# Ctrl.net
KiCad netlist of a schematic drawn in Altium Designer
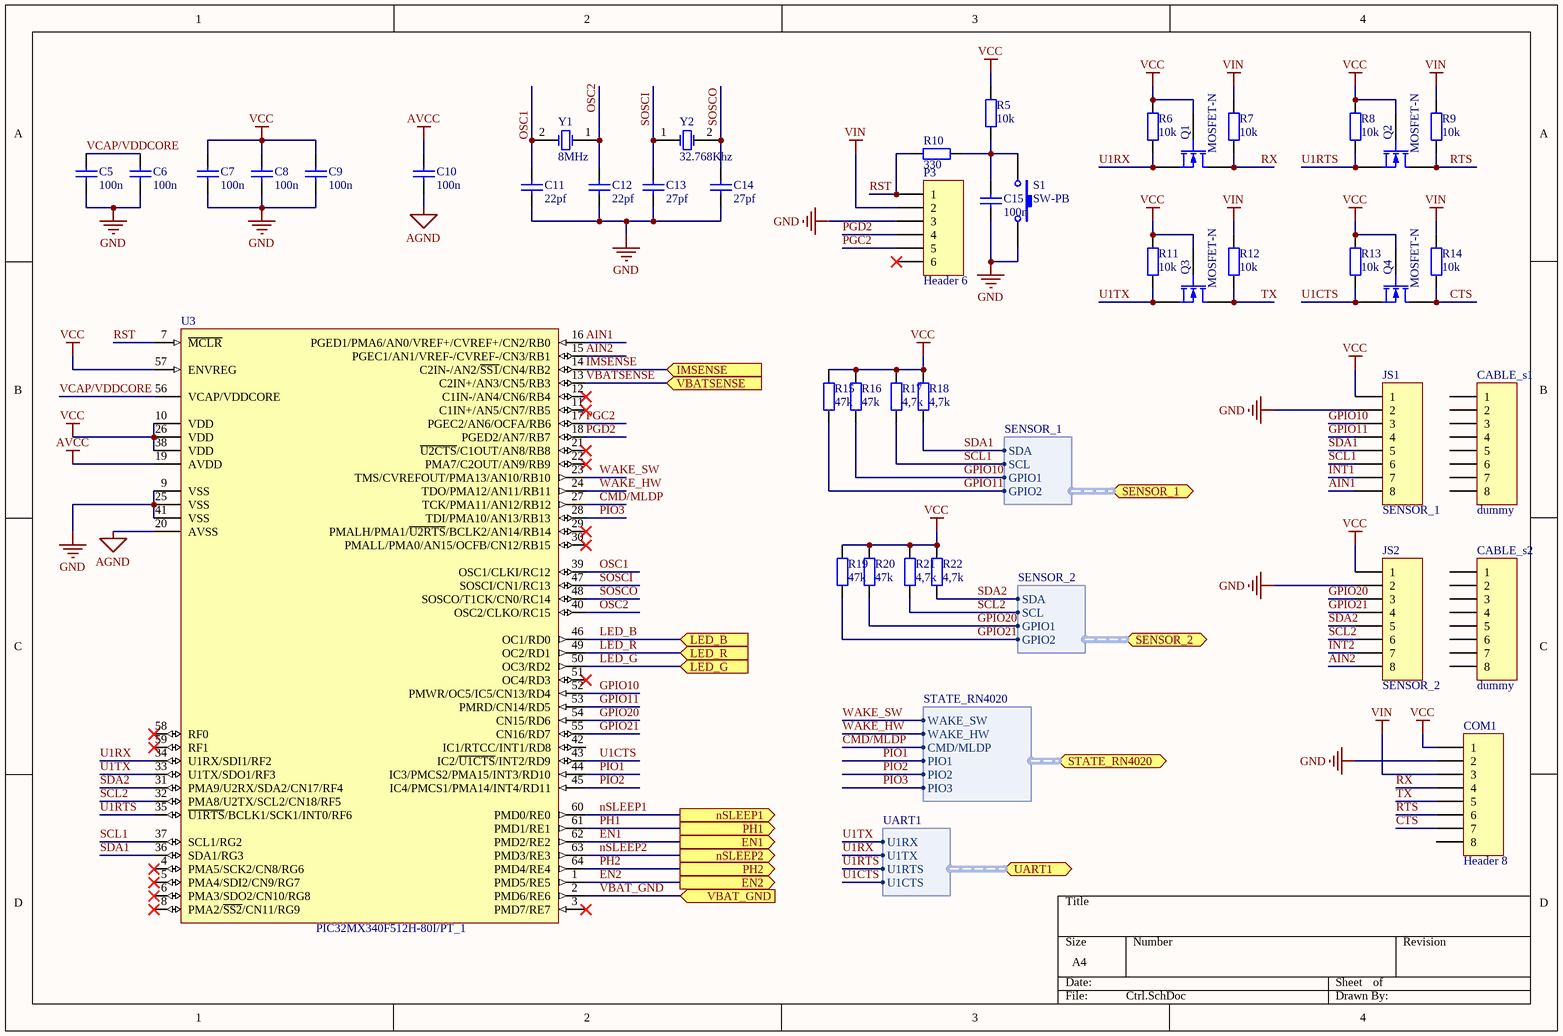
[diagram p0: Ctrl.SchDoc]

(export (version "E")
  (design (tool "Eeschema 10.0.6"))
  (components
    (comp (ref "C5")
      (value "100n")
      (footprint "RES 0603/1608")
      (libsource (lib "Miscellaneous Devices") (part "Cap"))
    )
    (comp (ref "C6")
      (value "100n")
      (footprint "RES 0603/1608")
      (libsource (lib "Miscellaneous Devices") (part "Cap"))
    )
    (comp (ref "C7")
      (value "100n")
      (footprint "RES 0603/1608")
      (libsource (lib "Miscellaneous Devices") (part "Cap"))
    )
    (comp (ref "C8")
      (value "100n")
      (footprint "RES 0603/1608")
      (libsource (lib "Miscellaneous Devices") (part "Cap"))
    )
    (comp (ref "C9")
      (value "100n")
      (footprint "RES 0603/1608")
      (libsource (lib "Miscellaneous Devices") (part "Cap"))
    )
    (comp (ref "C10")
      (value "100n")
      (footprint "RES 0603/1608")
      (libsource (lib "Miscellaneous Devices") (part "Cap"))
    )
    (comp (ref "C11")
      (value "22pf")
      (footprint "RES 0603/1608")
      (description "Condensateur céramique multicouche CMS, 0805 [2012 Metric], 22 pF, 50 V, ± 5%, C0G / NP0")
      (libsource (lib "Miscellaneous Devices") (part "Cap"))
    )
    (comp (ref "C12")
      (value "22pf")
      (footprint "RES 0603/1608")
      (description "Condensateur céramique multicouche CMS, 0805 [2012 Metric], 22 pF, 50 V, ± 5%, C0G / NP0")
      (libsource (lib "Miscellaneous Devices") (part "Cap"))
    )
    (comp (ref "C13")
      (value "27pf")
      (footprint "RES 0603/1608")
      (description "Condensateur céramique multicouche CMS, 0805 [2012 Metric], 27 pF, 50 V, ± 5%, C0G / NP0")
      (libsource (lib "Miscellaneous Devices") (part "Cap"))
    )
    (comp (ref "C14")
      (value "27pf")
      (footprint "RES 0603/1608")
      (description "Condensateur céramique multicouche CMS, 0805 [2012 Metric], 27 pF, 50 V, ± 5%, C0G / NP0")
      (libsource (lib "Miscellaneous Devices") (part "Cap"))
    )
    (comp (ref "C15")
      (value "100n")
      (footprint "RES 0603/1608")
      (libsource (lib "Miscellaneous Devices") (part "Cap"))
    )
    (comp (ref "CABLE_s1") (value "dummy") (libsource (lib "Miscellaneous Connectors") (part "Header 8")))
    (comp (ref "CABLE_s2") (value "dummy") (libsource (lib "Miscellaneous Connectors") (part "Header 8")))
    (comp (ref "COM1")
      (value "Header 8")
      (footprint "7-215460-8")
      (libsource (lib "Miscellaneous Connectors") (part "Header 8"))
    )
    (comp (ref "JS1")
      (value "SENSOR_1")
      (footprint "7-215460-8")
      (libsource (lib "Miscellaneous Connectors") (part "Header 8"))
    )
    (comp (ref "JS2")
      (value "SENSOR_2")
      (footprint "7-215460-8")
      (libsource (lib "Miscellaneous Connectors") (part "Header 8"))
    )
    (comp (ref "P3")
      (value "Header 6")
      (footprint "HDR1X6")
      (description "Header, 6-Pin")
      (libsource (lib "Miscellaneous Connectors") (part "Header 6"))
    )
    (comp (ref "Q1")
      (value "MOSFET-N")
      (footprint "SOT-23")
      (description "Transistor MOSFET, Canal N, 200 mA, 60 V, 2.7 ohm, 10 V, 1.2 V")
      (libsource (lib "Miscellaneous Devices") (part "MOSFET-N"))
    )
    (comp (ref "Q2")
      (value "MOSFET-N")
      (footprint "SOT-23")
      (description "Transistor MOSFET, Canal N, 200 mA, 60 V, 2.7 ohm, 10 V, 1.2 V")
      (libsource (lib "Miscellaneous Devices") (part "MOSFET-N"))
    )
    (comp (ref "Q3")
      (value "MOSFET-N")
      (footprint "SOT-23")
      (description "Transistor MOSFET, Canal N, 200 mA, 60 V, 2.7 ohm, 10 V, 1.2 V")
      (libsource (lib "Miscellaneous Devices") (part "MOSFET-N"))
    )
    (comp (ref "Q4")
      (value "MOSFET-N")
      (footprint "SOT-23")
      (description "Transistor MOSFET, Canal N, 200 mA, 60 V, 2.7 ohm, 10 V, 1.2 V")
      (libsource (lib "Miscellaneous Devices") (part "MOSFET-N"))
    )
    (comp (ref "R5")
      (value "10k")
      (footprint "RES 0603/1608")
      (description "Résistance à puce CMS, Couche épaisse, 10 kohm, 150 V, 0805")
      (libsource (lib "Miscellaneous Devices") (part "Res2"))
    )
    (comp (ref "R6")
      (value "10k")
      (footprint "RES 0603/1608")
      (description "Résistance à puce CMS, Couche épaisse, 10 kohm, 150 V, 0805")
      (libsource (lib "Miscellaneous Devices") (part "Res2"))
    )
    (comp (ref "R7")
      (value "10k")
      (footprint "RES 0603/1608")
      (description "Résistance à puce CMS, Couche épaisse, 10 kohm, 150 V, 0805")
      (libsource (lib "Miscellaneous Devices") (part "Res2"))
    )
    (comp (ref "R8")
      (value "10k")
      (footprint "RES 0603/1608")
      (description "Résistance à puce CMS, Couche épaisse, 10 kohm, 150 V, 0805")
      (libsource (lib "Miscellaneous Devices") (part "Res2"))
    )
    (comp (ref "R9")
      (value "10k")
      (footprint "RES 0603/1608")
      (description "Résistance à puce CMS, Couche épaisse, 10 kohm, 150 V, 0805")
      (libsource (lib "Miscellaneous Devices") (part "Res2"))
    )
    (comp (ref "R10") (value "330") (footprint "RES 0603/1608") (libsource (lib "") (part "Res2_1")))
    (comp (ref "R11")
      (value "10k")
      (footprint "RES 0603/1608")
      (description "Résistance à puce CMS, Couche épaisse, 10 kohm, 150 V, 0805")
      (libsource (lib "Miscellaneous Devices") (part "Res2"))
    )
    (comp (ref "R12")
      (value "10k")
      (footprint "RES 0603/1608")
      (description "Résistance à puce CMS, Couche épaisse, 10 kohm, 150 V, 0805")
      (libsource (lib "Miscellaneous Devices") (part "Res2"))
    )
    (comp (ref "R13")
      (value "10k")
      (footprint "RES 0603/1608")
      (description "Résistance à puce CMS, Couche épaisse, 10 kohm, 150 V, 0805")
      (libsource (lib "Miscellaneous Devices") (part "Res2"))
    )
    (comp (ref "R14")
      (value "10k")
      (footprint "RES 0603/1608")
      (description "Résistance à puce CMS, Couche épaisse, 10 kohm, 150 V, 0805")
      (libsource (lib "Miscellaneous Devices") (part "Res2"))
    )
    (comp (ref "R15")
      (value "47k")
      (footprint "RES 0603/1608")
      (description "Résistance à puce CMS, Couche épaisse, 47 kohm, 150 V, 0805 [2012 Metric], 125 mW, ± 1%, Série RC")
      (libsource (lib "Miscellaneous Devices") (part "Res2"))
    )
    (comp (ref "R16")
      (value "47k")
      (footprint "RES 0603/1608")
      (description "Résistance à puce CMS, Couche épaisse, 47 kohm, 150 V, 0805 [2012 Metric], 125 mW, ± 1%, Série RC")
      (libsource (lib "Miscellaneous Devices") (part "Res2"))
    )
    (comp (ref "R17")
      (value "4,7k")
      (footprint "RES 0603/1608")
      (description "Résistance à puce CMS, Couche épaisse, 4.7 kohm, 150 V, 0805 [2012 Metric], 125 mW, ± 5%, Série RC")
      (libsource (lib "Miscellaneous Devices") (part "Res2"))
    )
    (comp (ref "R18")
      (value "4,7k")
      (footprint "RES 0603/1608")
      (description "Résistance à puce CMS, Couche épaisse, 4.7 kohm, 150 V, 0805 [2012 Metric], 125 mW, ± 5%, Série RC")
      (libsource (lib "Miscellaneous Devices") (part "Res2"))
    )
    (comp (ref "R19")
      (value "47k")
      (footprint "RES 0603/1608")
      (description "Résistance à puce CMS, Couche épaisse, 47 kohm, 150 V, 0805 [2012 Metric], 125 mW, ± 1%, Série RC")
      (libsource (lib "Miscellaneous Devices") (part "Res2"))
    )
    (comp (ref "R20")
      (value "47k")
      (footprint "RES 0603/1608")
      (description "Résistance à puce CMS, Couche épaisse, 47 kohm, 150 V, 0805 [2012 Metric], 125 mW, ± 1%, Série RC")
      (libsource (lib "Miscellaneous Devices") (part "Res2"))
    )
    (comp (ref "R21")
      (value "4,7k")
      (footprint "RES 0603/1608")
      (description "Résistance à puce CMS, Couche épaisse, 4.7 kohm, 150 V, 0805 [2012 Metric], 125 mW, ± 5%, Série RC")
      (libsource (lib "Miscellaneous Devices") (part "Res2"))
    )
    (comp (ref "R22")
      (value "4,7k")
      (footprint "RES 0603/1608")
      (description "Résistance à puce CMS, Couche épaisse, 4.7 kohm, 150 V, 0805 [2012 Metric], 125 mW, ± 5%, Série RC")
      (libsource (lib "Miscellaneous Devices") (part "Res2"))
    )
    (comp (ref "S1")
      (value "SW-PB")
      (footprint "Button")
      (description "Commutateur tactile, Non lumineux, 12 V, 50 mA, 100 gf, CMS, Série DTSZML-6")
      (libsource (lib "Miscellaneous Devices") (part "SW-PB"))
    )
    (comp (ref "U3")
      (value "PIC32MX340F512H-80I/PT_1")
      (footprint "TSQFP50P1200X1200X120-64N")
      (description "High Performance 80 MHz MIPS-Based 32-Bit Flash Microcontroller, 512KB Program Memory, 64-pin TQFP")
      (libsource (lib "ComponentLib") (part "PIC32MX340F512H-80I/PT_1"))
    )
    (comp (ref "Y1")
      (value "8MHz")
      (footprint "XTAL_HC-49/SM")
      (libsource (lib "Miscellaneous Devices") (part "XTAL"))
    )
    (comp (ref "Y2")
      (value "32.768Khz")
      (footprint "XTAL_AB26T")
      (libsource (lib "Miscellaneous Devices") (part "XTAL"))
    )
  )
  (nets
    (net (code "5") (name "/AIN1") (class "Default")
      (node (ref "JS1") (pin "8") (pinfunction "8_8") (pintype "passive"))
      (node (ref "U3") (pin "16") (pinfunction "PGED1/PMA6/AN0/VREF+/CVREF+/CN2/RB0_16") (pintype "input"))
    )
    (net (code "6") (name "/AIN2") (class "Default")
      (node (ref "JS2") (pin "8") (pinfunction "8_8") (pintype "passive"))
      (node (ref "U3") (pin "15") (pinfunction "PGEC1/AN1/VREF-/CVREF-/CN3/RB1_15") (pintype "bidirectional"))
    )
    (net (code "7") (name "/CMD{slash}MLDP") (class "Default")
      (node (ref "U3") (pin "27") (pinfunction "TCK/PMA11/AN12/RB12_27") (pintype "output"))
    )
    (net (code "8") (name "/CTS") (class "Default")
      (node (ref "COM1") (pin "7") (pinfunction "7_7") (pintype "passive"))
      (node (ref "Q4") (pin "1") (pinfunction "D_1") (pintype "passive"))
      (node (ref "R14") (pin "1") (pinfunction "1_1") (pintype "passive"))
    )
    (net (code "9") (name "/EN1") (class "Default")
      (node (ref "U3") (pin "62") (pinfunction "PMD2/RE2_62") (pintype "output"))
    )
    (net (code "10") (name "/EN2") (class "Default")
      (node (ref "U3") (pin "1") (pinfunction "PMD5/RE5_1") (pintype "output"))
    )
    (net (code "11") (name "/GPIO10") (class "Default")
      (node (ref "JS1") (pin "3") (pinfunction "3_3") (pintype "passive"))
      (node (ref "R16") (pin "1") (pinfunction "1_1") (pintype "passive"))
      (node (ref "U3") (pin "52") (pinfunction "PMWR/OC5/IC5/CN13/RD4_52") (pintype "input"))
    )
    (net (code "12") (name "/GPIO11") (class "Default")
      (node (ref "JS1") (pin "4") (pinfunction "4_4") (pintype "passive"))
      (node (ref "R15") (pin "1") (pinfunction "1_1") (pintype "passive"))
      (node (ref "U3") (pin "53") (pinfunction "PMRD/CN14/RD5_53") (pintype "input"))
    )
    (net (code "13") (name "/GPIO20") (class "Default")
      (node (ref "JS2") (pin "3") (pinfunction "3_3") (pintype "passive"))
      (node (ref "R20") (pin "1") (pinfunction "1_1") (pintype "passive"))
      (node (ref "U3") (pin "54") (pinfunction "CN15/RD6_54") (pintype "input"))
    )
    (net (code "14") (name "/GPIO21") (class "Default")
      (node (ref "JS2") (pin "4") (pinfunction "4_4") (pintype "passive"))
      (node (ref "R19") (pin "1") (pinfunction "1_1") (pintype "passive"))
      (node (ref "U3") (pin "55") (pinfunction "CN16/RD7_55") (pintype "bidirectional"))
    )
    (net (code "15") (name "/IMSENSE") (class "Default")
      (node (ref "U3") (pin "14") (pinfunction "C2IN-/AN2/~{SS1}/CN4/RB2_14") (pintype "bidirectional"))
    )
    (net (code "16") (name "/INT1") (class "Default")
      (node (ref "JS1") (pin "7") (pinfunction "7_7") (pintype "passive"))
    )
    (net (code "17") (name "/INT2") (class "Default")
      (node (ref "JS2") (pin "7") (pinfunction "7_7") (pintype "passive"))
    )
    (net (code "18") (name "/LED_B") (class "Default")
      (node (ref "U3") (pin "46") (pinfunction "OC1/RD0_46") (pintype "output"))
    )
    (net (code "19") (name "/LED_G") (class "Default")
      (node (ref "U3") (pin "50") (pinfunction "OC3/RD2_50") (pintype "output"))
    )
    (net (code "20") (name "/LED_R") (class "Default")
      (node (ref "U3") (pin "49") (pinfunction "OC2/RD1_49") (pintype "output"))
    )
    (net (code "21") (name "/OSC1") (class "Default")
      (node (ref "C11") (pin "1") (pinfunction "1_1") (pintype "passive"))
      (node (ref "U3") (pin "39") (pinfunction "OSC1/CLKI/RC12_39") (pintype "bidirectional"))
      (node (ref "Y1") (pin "2") (pinfunction "OSC2_2") (pintype "passive"))
    )
    (net (code "22") (name "/OSC2") (class "Default")
      (node (ref "C12") (pin "1") (pinfunction "1_1") (pintype "passive"))
      (node (ref "U3") (pin "40") (pinfunction "OSC2/CLKO/RC15_40") (pintype "bidirectional"))
      (node (ref "Y1") (pin "1") (pinfunction "OSC1_1") (pintype "passive"))
    )
    (net (code "23") (name "/PGC2") (class "Default")
      (node (ref "P3") (pin "5") (pinfunction "5_5") (pintype "passive"))
      (node (ref "U3") (pin "17") (pinfunction "PGEC2/AN6/OCFA/RB6_17") (pintype "bidirectional"))
    )
    (net (code "24") (name "/PGD2") (class "Default")
      (node (ref "P3") (pin "4") (pinfunction "4_4") (pintype "passive"))
      (node (ref "U3") (pin "18") (pinfunction "PGED2/AN7/RB7_18") (pintype "bidirectional"))
    )
    (net (code "25") (name "/PH1") (class "Default")
      (node (ref "U3") (pin "61") (pinfunction "PMD1/RE1_61") (pintype "output"))
    )
    (net (code "26") (name "/PH2") (class "Default")
      (node (ref "U3") (pin "64") (pinfunction "PMD4/RE4_64") (pintype "output"))
    )
    (net (code "27") (name "/PIO1") (class "Default")
      (node (ref "U3") (pin "44") (pinfunction "IC3/PMCS2/PMA15/INT3/RD10_44") (pintype "input"))
    )
    (net (code "28") (name "/PIO2") (class "Default")
      (node (ref "U3") (pin "45") (pinfunction "IC4/PMCS1/PMA14/INT4/RD11_45") (pintype "input"))
    )
    (net (code "29") (name "/PIO3") (class "Default")
      (node (ref "U3") (pin "28") (pinfunction "TDI/PMA10/AN13/RB13_28") (pintype "bidirectional"))
    )
    (net (code "30") (name "/RST") (class "Default")
      (node (ref "P3") (pin "1") (pinfunction "1_1") (pintype "passive"))
      (node (ref "R10") (pin "1") (pinfunction "1_1") (pintype "passive"))
      (node (ref "U3") (pin "7") (pinfunction "~{MCLR}_7") (pintype "input"))
    )
    (net (code "31") (name "/RTS") (class "Default")
      (node (ref "COM1") (pin "6") (pinfunction "6_6") (pintype "passive"))
      (node (ref "Q2") (pin "1") (pinfunction "D_1") (pintype "passive"))
      (node (ref "R9") (pin "1") (pinfunction "1_1") (pintype "passive"))
    )
    (net (code "32") (name "/RX") (class "Default")
      (node (ref "COM1") (pin "4") (pinfunction "4_4") (pintype "passive"))
      (node (ref "Q1") (pin "1") (pinfunction "D_1") (pintype "passive"))
      (node (ref "R7") (pin "1") (pinfunction "1_1") (pintype "passive"))
    )
    (net (code "33") (name "/SCL1") (class "Default")
      (node (ref "JS1") (pin "6") (pinfunction "6_6") (pintype "passive"))
      (node (ref "R17") (pin "1") (pinfunction "1_1") (pintype "passive"))
      (node (ref "U3") (pin "37") (pinfunction "SCL1/RG2_37") (pintype "bidirectional"))
    )
    (net (code "34") (name "/SCL2") (class "Default")
      (node (ref "JS2") (pin "6") (pinfunction "6_6") (pintype "passive"))
      (node (ref "R21") (pin "1") (pinfunction "1_1") (pintype "passive"))
      (node (ref "U3") (pin "32") (pinfunction "PMA8/U2TX/SCL2/CN18/RF5_32") (pintype "bidirectional"))
    )
    (net (code "35") (name "/SDA1") (class "Default")
      (node (ref "JS1") (pin "5") (pinfunction "5_5") (pintype "passive"))
      (node (ref "R18") (pin "1") (pinfunction "1_1") (pintype "passive"))
      (node (ref "U3") (pin "36") (pinfunction "SDA1/RG3_36") (pintype "bidirectional"))
    )
    (net (code "36") (name "/SDA2") (class "Default")
      (node (ref "JS2") (pin "5") (pinfunction "5_5") (pintype "passive"))
      (node (ref "R22") (pin "1") (pinfunction "1_1") (pintype "passive"))
      (node (ref "U3") (pin "31") (pinfunction "PMA9/U2RX/SDA2/CN17/RF4_31") (pintype "bidirectional"))
    )
    (net (code "37") (name "/SOSCI") (class "Default")
      (node (ref "C13") (pin "1") (pinfunction "1_1") (pintype "passive"))
      (node (ref "U3") (pin "47") (pinfunction "SOSCI/CN1/RC13_47") (pintype "bidirectional"))
      (node (ref "Y2") (pin "1") (pinfunction "OSC1_1") (pintype "passive"))
    )
    (net (code "38") (name "/SOSCO") (class "Default")
      (node (ref "C14") (pin "1") (pinfunction "1_1") (pintype "passive"))
      (node (ref "U3") (pin "48") (pinfunction "SOSCO/T1CK/CN0/RC14_48") (pintype "bidirectional"))
      (node (ref "Y2") (pin "2") (pinfunction "OSC2_2") (pintype "passive"))
    )
    (net (code "39") (name "/TX") (class "Default")
      (node (ref "COM1") (pin "5") (pinfunction "5_5") (pintype "passive"))
      (node (ref "Q3") (pin "1") (pinfunction "D_1") (pintype "passive"))
      (node (ref "R12") (pin "1") (pinfunction "1_1") (pintype "passive"))
    )
    (net (code "40") (name "/U1CTS") (class "Default")
      (node (ref "Q4") (pin "3") (pinfunction "S_3") (pintype "passive"))
      (node (ref "R13") (pin "1") (pinfunction "1_1") (pintype "passive"))
      (node (ref "U3") (pin "43") (pinfunction "IC2/~{U1CTS}/INT2/RD9_43") (pintype "bidirectional"))
    )
    (net (code "41") (name "/U1RTS") (class "Default")
      (node (ref "Q2") (pin "3") (pinfunction "S_3") (pintype "passive"))
      (node (ref "R8") (pin "1") (pinfunction "1_1") (pintype "passive"))
      (node (ref "U3") (pin "35") (pinfunction "~{U1RTS}/BCLK1/SCK1/INT0/RF6_35") (pintype "bidirectional"))
    )
    (net (code "42") (name "/U1RX") (class "Default")
      (node (ref "Q1") (pin "3") (pinfunction "S_3") (pintype "passive"))
      (node (ref "R6") (pin "1") (pinfunction "1_1") (pintype "passive"))
      (node (ref "U3") (pin "34") (pinfunction "U1RX/SDI1/RF2_34") (pintype "bidirectional"))
    )
    (net (code "43") (name "/U1TX") (class "Default")
      (node (ref "Q3") (pin "3") (pinfunction "S_3") (pintype "passive"))
      (node (ref "R11") (pin "1") (pinfunction "1_1") (pintype "passive"))
      (node (ref "U3") (pin "33") (pinfunction "U1TX/SDO1/RF3_33") (pintype "bidirectional"))
    )
    (net (code "44") (name "/VBATSENSE") (class "Default")
      (node (ref "U3") (pin "13") (pinfunction "C2IN+/AN3/CN5/RB3_13") (pintype "bidirectional"))
    )
    (net (code "45") (name "/VBAT_GND") (class "Default")
      (node (ref "U3") (pin "2") (pinfunction "PMD6/RE6_2") (pintype "output"))
    )
    (net (code "46") (name "/VCAP{slash}VDDCORE") (class "Default")
      (node (ref "C5") (pin "1") (pinfunction "1_1") (pintype "passive"))
      (node (ref "C6") (pin "1") (pinfunction "1_1") (pintype "passive"))
      (node (ref "U3") (pin "56") (pinfunction "VCAP/VDDCORE_56") (pintype "power_in"))
    )
    (net (code "47") (name "/WAKE_HW") (class "Default")
      (node (ref "U3") (pin "24") (pinfunction "TDO/PMA12/AN11/RB11_24") (pintype "output"))
    )
    (net (code "48") (name "/WAKE_SW") (class "Default")
      (node (ref "U3") (pin "23") (pinfunction "TMS/CVREFOUT/PMA13/AN10/RB10_23") (pintype "output"))
    )
    (net (code "49") (name "/nSLEEP1") (class "Default")
      (node (ref "U3") (pin "60") (pinfunction "PMD0/RE0_60") (pintype "output"))
    )
    (net (code "50") (name "/nSLEEP2") (class "Default")
      (node (ref "U3") (pin "63") (pinfunction "PMD3/RE3_63") (pintype "output"))
    )
    (net (code "55") (name "AGND") (class "Default")
      (node (ref "C10") (pin "2") (pinfunction "2_2") (pintype "passive"))
      (node (ref "U3") (pin "20") (pinfunction "AVSS_20") (pintype "power_in"))
    )
    (net (code "56") (name "AVCC") (class "Default")
      (node (ref "C10") (pin "1") (pinfunction "1_1") (pintype "passive"))
      (node (ref "U3") (pin "19") (pinfunction "AVDD_19") (pintype "power_in"))
    )
    (net (code "57") (name "GND") (class "Default")
      (node (ref "C11") (pin "2") (pinfunction "2_2") (pintype "passive"))
      (node (ref "C12") (pin "2") (pinfunction "2_2") (pintype "passive"))
      (node (ref "C13") (pin "2") (pinfunction "2_2") (pintype "passive"))
      (node (ref "C14") (pin "2") (pinfunction "2_2") (pintype "passive"))
      (node (ref "C15") (pin "2") (pinfunction "2_2") (pintype "passive"))
      (node (ref "C5") (pin "2") (pinfunction "2_2") (pintype "passive"))
      (node (ref "C6") (pin "2") (pinfunction "2_2") (pintype "passive"))
      (node (ref "C7") (pin "2") (pinfunction "2_2") (pintype "passive"))
      (node (ref "C8") (pin "2") (pinfunction "2_2") (pintype "passive"))
      (node (ref "C9") (pin "2") (pinfunction "2_2") (pintype "passive"))
      (node (ref "COM1") (pin "2") (pinfunction "2_2") (pintype "passive"))
      (node (ref "JS1") (pin "2") (pinfunction "2_2") (pintype "passive"))
      (node (ref "JS2") (pin "2") (pinfunction "2_2") (pintype "passive"))
      (node (ref "P3") (pin "3") (pinfunction "3_3") (pintype "passive"))
      (node (ref "S1") (pin "2") (pinfunction "2_2") (pintype "passive"))
      (node (ref "U3") (pin "25") (pinfunction "VSS_25") (pintype "power_in"))
      (node (ref "U3") (pin "41") (pinfunction "VSS_41") (pintype "power_in"))
      (node (ref "U3") (pin "9") (pinfunction "VSS_9") (pintype "power_in"))
    )
    (net (code "58") (name "Net-(C15-Pad1)") (class "Default")
      (node (ref "C15") (pin "1") (pinfunction "1_1") (pintype "passive"))
      (node (ref "R10") (pin "2") (pinfunction "2_2") (pintype "passive"))
      (node (ref "R5") (pin "1") (pinfunction "1_1") (pintype "passive"))
      (node (ref "S1") (pin "1") (pinfunction "1_1") (pintype "passive"))
    )
    (net (code "59") (name "VCC") (class "Default")
      (node (ref "C7") (pin "1") (pinfunction "1_1") (pintype "passive"))
      (node (ref "C8") (pin "1") (pinfunction "1_1") (pintype "passive"))
      (node (ref "C9") (pin "1") (pinfunction "1_1") (pintype "passive"))
      (node (ref "COM1") (pin "1") (pinfunction "1_1") (pintype "passive"))
      (node (ref "JS1") (pin "1") (pinfunction "1_1") (pintype "passive"))
      (node (ref "JS2") (pin "1") (pinfunction "1_1") (pintype "passive"))
      (node (ref "Q1") (pin "2") (pinfunction "G_2") (pintype "passive"))
      (node (ref "Q2") (pin "2") (pinfunction "G_2") (pintype "passive"))
      (node (ref "Q3") (pin "2") (pinfunction "G_2") (pintype "passive"))
      (node (ref "Q4") (pin "2") (pinfunction "G_2") (pintype "passive"))
      (node (ref "R11") (pin "2") (pinfunction "2_2") (pintype "passive"))
      (node (ref "R13") (pin "2") (pinfunction "2_2") (pintype "passive"))
      (node (ref "R15") (pin "2") (pinfunction "2_2") (pintype "passive"))
      (node (ref "R16") (pin "2") (pinfunction "2_2") (pintype "passive"))
      (node (ref "R17") (pin "2") (pinfunction "2_2") (pintype "passive"))
      (node (ref "R18") (pin "2") (pinfunction "2_2") (pintype "passive"))
      (node (ref "R19") (pin "2") (pinfunction "2_2") (pintype "passive"))
      (node (ref "R20") (pin "2") (pinfunction "2_2") (pintype "passive"))
      (node (ref "R21") (pin "2") (pinfunction "2_2") (pintype "passive"))
      (node (ref "R22") (pin "2") (pinfunction "2_2") (pintype "passive"))
      (node (ref "R5") (pin "2") (pinfunction "2_2") (pintype "passive"))
      (node (ref "R6") (pin "2") (pinfunction "2_2") (pintype "passive"))
      (node (ref "R8") (pin "2") (pinfunction "2_2") (pintype "passive"))
      (node (ref "U3") (pin "10") (pinfunction "VDD_10") (pintype "power_in"))
      (node (ref "U3") (pin "26") (pinfunction "VDD_26") (pintype "power_in"))
      (node (ref "U3") (pin "38") (pinfunction "VDD_38") (pintype "power_in"))
      (node (ref "U3") (pin "57") (pinfunction "ENVREG_57") (pintype "input"))
    )
    (net (code "60") (name "VIN") (class "Default")
      (node (ref "COM1") (pin "3") (pinfunction "3_3") (pintype "passive"))
      (node (ref "P3") (pin "2") (pinfunction "2_2") (pintype "passive"))
      (node (ref "R12") (pin "2") (pinfunction "2_2") (pintype "passive"))
      (node (ref "R14") (pin "2") (pinfunction "2_2") (pintype "passive"))
      (node (ref "R7") (pin "2") (pinfunction "2_2") (pintype "passive"))
      (node (ref "R9") (pin "2") (pinfunction "2_2") (pintype "passive"))
    )
    (net (code "61") (name "unconnected-(CABLE_s1-Pad1)") (class "Default")
      (node (ref "CABLE_s1") (pin "1") (pinfunction "1_1") (pintype "passive"))
    )
    (net (code "62") (name "unconnected-(CABLE_s1-Pad2)") (class "Default")
      (node (ref "CABLE_s1") (pin "2") (pinfunction "2_2") (pintype "passive"))
    )
    (net (code "63") (name "unconnected-(CABLE_s1-Pad3)") (class "Default")
      (node (ref "CABLE_s1") (pin "3") (pinfunction "3_3") (pintype "passive"))
    )
    (net (code "64") (name "unconnected-(CABLE_s1-Pad4)") (class "Default")
      (node (ref "CABLE_s1") (pin "4") (pinfunction "4_4") (pintype "passive"))
    )
    (net (code "65") (name "unconnected-(CABLE_s1-Pad5)") (class "Default")
      (node (ref "CABLE_s1") (pin "5") (pinfunction "5_5") (pintype "passive"))
    )
    (net (code "66") (name "unconnected-(CABLE_s1-Pad6)") (class "Default")
      (node (ref "CABLE_s1") (pin "6") (pinfunction "6_6") (pintype "passive"))
    )
    (net (code "67") (name "unconnected-(CABLE_s1-Pad7)") (class "Default")
      (node (ref "CABLE_s1") (pin "7") (pinfunction "7_7") (pintype "passive"))
    )
    (net (code "68") (name "unconnected-(CABLE_s1-Pad8)") (class "Default")
      (node (ref "CABLE_s1") (pin "8") (pinfunction "8_8") (pintype "passive"))
    )
    (net (code "69") (name "unconnected-(CABLE_s2-Pad1)") (class "Default")
      (node (ref "CABLE_s2") (pin "1") (pinfunction "1_1") (pintype "passive"))
    )
    (net (code "70") (name "unconnected-(CABLE_s2-Pad2)") (class "Default")
      (node (ref "CABLE_s2") (pin "2") (pinfunction "2_2") (pintype "passive"))
    )
    (net (code "71") (name "unconnected-(CABLE_s2-Pad3)") (class "Default")
      (node (ref "CABLE_s2") (pin "3") (pinfunction "3_3") (pintype "passive"))
    )
    (net (code "72") (name "unconnected-(CABLE_s2-Pad4)") (class "Default")
      (node (ref "CABLE_s2") (pin "4") (pinfunction "4_4") (pintype "passive"))
    )
    (net (code "73") (name "unconnected-(CABLE_s2-Pad5)") (class "Default")
      (node (ref "CABLE_s2") (pin "5") (pinfunction "5_5") (pintype "passive"))
    )
    (net (code "74") (name "unconnected-(CABLE_s2-Pad6)") (class "Default")
      (node (ref "CABLE_s2") (pin "6") (pinfunction "6_6") (pintype "passive"))
    )
    (net (code "75") (name "unconnected-(CABLE_s2-Pad7)") (class "Default")
      (node (ref "CABLE_s2") (pin "7") (pinfunction "7_7") (pintype "passive"))
    )
    (net (code "76") (name "unconnected-(CABLE_s2-Pad8)") (class "Default")
      (node (ref "CABLE_s2") (pin "8") (pinfunction "8_8") (pintype "passive"))
    )
    (net (code "77") (name "unconnected-(COM1-Pad8)") (class "Default")
      (node (ref "COM1") (pin "8") (pinfunction "8_8") (pintype "passive"))
    )
    (net (code "78") (name "unconnected-(P3-Pad6)") (class "Default")
      (node (ref "P3") (pin "6") (pinfunction "6_6") (pintype "passive+no_connect"))
    )
    (net (code "79") (name "unconnected-(U3-C1IN+{slash}AN5{slash}CN7{slash}RB5-Pad11)") (class "Default")
      (node (ref "U3") (pin "11") (pinfunction "C1IN+/AN5/CN7/RB5_11") (pintype "bidirectional+no_connect"))
    )
    (net (code "80") (name "unconnected-(U3-C1IN-{slash}AN4{slash}CN6{slash}RB4-Pad12)") (class "Default")
      (node (ref "U3") (pin "12") (pinfunction "C1IN-/AN4/CN6/RB4_12") (pintype "bidirectional+no_connect"))
    )
    (net (code "81") (name "unconnected-(U3-IC1{slash}RTCC{slash}INT1{slash}RD8-Pad42)") (class "Default")
      (node (ref "U3") (pin "42") (pinfunction "IC1/RTCC/INT1/RD8_42") (pintype "bidirectional"))
    )
    (net (code "82") (name "unconnected-(U3-OC4{slash}RD3-Pad51)") (class "Default")
      (node (ref "U3") (pin "51") (pinfunction "OC4/RD3_51") (pintype "bidirectional+no_connect"))
    )
    (net (code "83") (name "unconnected-(U3-PMA2{slash}~{SS2}{slash}CN11{slash}RG9-Pad8)") (class "Default")
      (node (ref "U3") (pin "8") (pinfunction "PMA2/~{SS2}/CN11/RG9_8") (pintype "bidirectional+no_connect"))
    )
    (net (code "84") (name "unconnected-(U3-PMA3{slash}SDO2{slash}CN10{slash}RG8-Pad6)") (class "Default")
      (node (ref "U3") (pin "6") (pinfunction "PMA3/SDO2/CN10/RG8_6") (pintype "bidirectional+no_connect"))
    )
    (net (code "85") (name "unconnected-(U3-PMA4{slash}SDI2{slash}CN9{slash}RG7-Pad5)") (class "Default")
      (node (ref "U3") (pin "5") (pinfunction "PMA4/SDI2/CN9/RG7_5") (pintype "bidirectional+no_connect"))
    )
    (net (code "86") (name "unconnected-(U3-PMA5{slash}SCK2{slash}CN8{slash}RG6-Pad4)") (class "Default")
      (node (ref "U3") (pin "4") (pinfunction "PMA5/SCK2/CN8/RG6_4") (pintype "bidirectional+no_connect"))
    )
    (net (code "87") (name "unconnected-(U3-PMA7{slash}C2OUT{slash}AN9{slash}RB9-Pad22)") (class "Default")
      (node (ref "U3") (pin "22") (pinfunction "PMA7/C2OUT/AN9/RB9_22") (pintype "bidirectional+no_connect"))
    )
    (net (code "88") (name "unconnected-(U3-PMALH{slash}PMA1{slash}~{U2RTS}{slash}BCLK2{slash}AN14{slash}RB14-Pad29)") (class "Default")
      (node (ref "U3") (pin "29") (pinfunction "PMALH/PMA1/~{U2RTS}/BCLK2/AN14/RB14_29") (pintype "bidirectional+no_connect"))
    )
    (net (code "89") (name "unconnected-(U3-PMALL{slash}PMA0{slash}AN15{slash}OCFB{slash}CN12{slash}RB15-Pad30)") (class "Default")
      (node (ref "U3") (pin "30") (pinfunction "PMALL/PMA0/AN15/OCFB/CN12/RB15_30") (pintype "bidirectional+no_connect"))
    )
    (net (code "90") (name "unconnected-(U3-PMD7{slash}RE7-Pad3)") (class "Default")
      (node (ref "U3") (pin "3") (pinfunction "PMD7/RE7_3") (pintype "input+no_connect"))
    )
    (net (code "91") (name "unconnected-(U3-RF0-Pad58)") (class "Default")
      (node (ref "U3") (pin "58") (pinfunction "RF0_58") (pintype "bidirectional+no_connect"))
    )
    (net (code "92") (name "unconnected-(U3-RF1-Pad59)") (class "Default")
      (node (ref "U3") (pin "59") (pinfunction "RF1_59") (pintype "bidirectional+no_connect"))
    )
    (net (code "93") (name "unconnected-(U3-~{U2CTS}{slash}C1OUT{slash}AN8{slash}RB8-Pad21)") (class "Default")
      (node (ref "U3") (pin "21") (pinfunction "~{U2CTS}/C1OUT/AN8/RB8_21") (pintype "bidirectional+no_connect"))
    )
  )
)
